# Sheet_CL-RB-01.net
KiCad netlist of a schematic drawn in Altium Designer
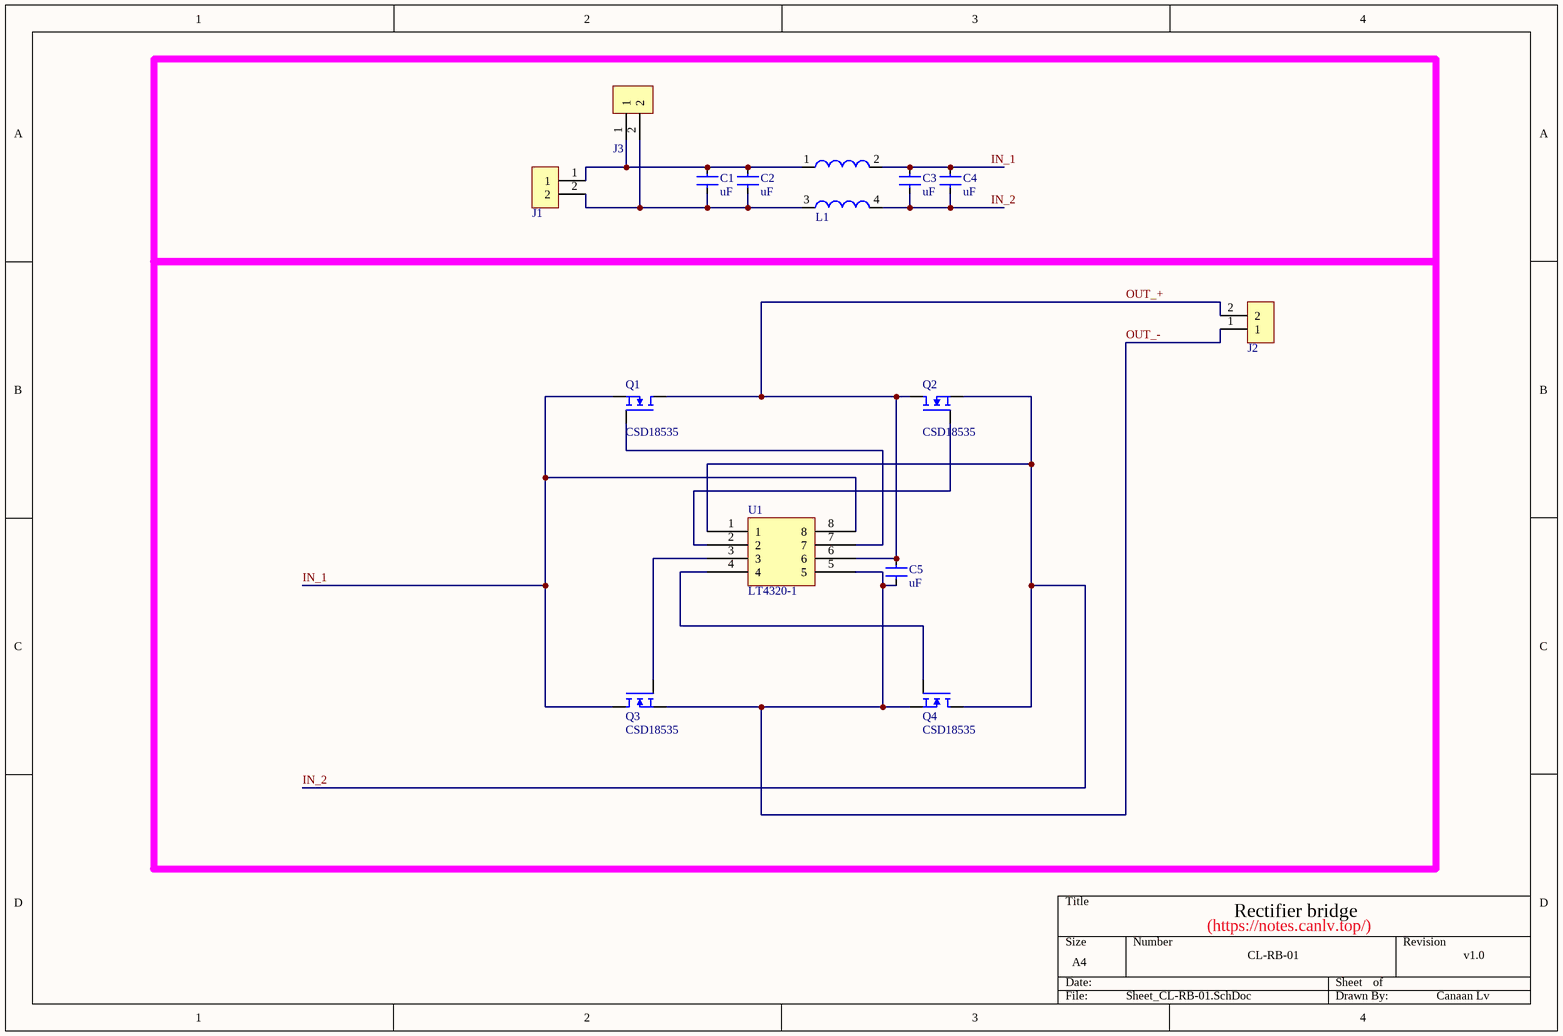
[diagram p0: Sheet_CL-RB-01.SchDoc]

(export (version "E")
  (design (tool "Eeschema 10.0.6"))
  (components
    (comp (ref "C1") (value "uF") (footprint "CAP-7.5-CP") (libsource (lib "电容") (part "C直插无极性")))
    (comp (ref "C2") (value "uF") (footprint "CAP-15") (libsource (lib "电容") (part "C直插无极性")))
    (comp (ref "C3") (value "uF") (footprint "CAP-15") (libsource (lib "电容") (part "C直插无极性")))
    (comp (ref "C4") (value "uF") (footprint "CAP-7.5-CP") (libsource (lib "电容") (part "C直插无极性")))
    (comp (ref "C5") (value "uF") (footprint "C0.254") (libsource (lib "电容") (part "C直插无极性")))
    (comp (ref "J1") (value "SIP-2") (footprint "9.5栅栏式接线端子") (libsource (lib "") (part "SIP-2_1")))
    (comp (ref "J2") (value "SIP-2") (footprint "9.5栅栏式接线端子") (libsource (lib "接插件") (part "SIP-2")))
    (comp (ref "J3") (value "SIP-2") (footprint "2.54XH接插件2P") (libsource (lib "接插件") (part "SIP-2")))
    (comp (ref "L1") (value "双电感") (footprint "L-CM(25*15*12)") (libsource (lib "电感") (part "双电感")))
    (comp (ref "Q1")
      (value "CSD18535")
      (footprint "TO-263-2")
      (description "N-Channel MOSFET")
      (libsource (lib "General") (part "N-MOSFET"))
    )
    (comp (ref "Q2")
      (value "CSD18535")
      (footprint "TO-263-2")
      (description "N-Channel MOSFET")
      (libsource (lib "General") (part "N-MOSFET"))
    )
    (comp (ref "Q3")
      (value "CSD18535")
      (footprint "TO-263-2")
      (description "N-Channel MOSFET")
      (libsource (lib "General") (part "N-MOSFET"))
    )
    (comp (ref "Q4")
      (value "CSD18535")
      (footprint "TO-263-2")
      (description "N-Channel MOSFET")
      (libsource (lib "General") (part "N-MOSFET"))
    )
    (comp (ref "U1") (value "LT4320-1") (footprint "DIP8") (libsource (lib "集成块") (part "IC8")))
  )
  (nets
    (net (code "1") (name "/IN_1") (class "Default")
      (node (ref "C3") (pin "1") (pinfunction "1_1") (pintype "passive"))
      (node (ref "C4") (pin "1") (pinfunction "1_1") (pintype "passive"))
      (node (ref "L1") (pin "2") (pinfunction "2_2") (pintype "passive"))
      (node (ref "Q1") (pin "3") (pinfunction "S_3") (pintype "passive"))
      (node (ref "Q3") (pin "2") (pinfunction "D_2") (pintype "passive"))
      (node (ref "U1") (pin "8") (pinfunction "8_8") (pintype "passive"))
    )
    (net (code "2") (name "/IN_2") (class "Default")
      (node (ref "C3") (pin "2") (pinfunction "2_2") (pintype "passive"))
      (node (ref "C4") (pin "2") (pinfunction "2_2") (pintype "passive"))
      (node (ref "L1") (pin "4") (pinfunction "4_4") (pintype "passive"))
      (node (ref "Q2") (pin "3") (pinfunction "S_3") (pintype "passive"))
      (node (ref "Q4") (pin "2") (pinfunction "D_2") (pintype "passive"))
      (node (ref "U1") (pin "1") (pinfunction "1_1") (pintype "passive"))
    )
    (net (code "3") (name "/OUT_+") (class "Default")
      (node (ref "C5") (pin "1") (pinfunction "1_1") (pintype "passive"))
      (node (ref "J2") (pin "2") (pinfunction "2_2") (pintype "passive"))
      (node (ref "Q1") (pin "2") (pinfunction "D_2") (pintype "passive"))
      (node (ref "Q2") (pin "2") (pinfunction "D_2") (pintype "passive"))
      (node (ref "U1") (pin "6") (pinfunction "6_6") (pintype "passive"))
    )
    (net (code "4") (name "/OUT_-") (class "Default")
      (node (ref "C5") (pin "2") (pinfunction "2_2") (pintype "passive"))
      (node (ref "J2") (pin "1") (pinfunction "1_1") (pintype "passive"))
      (node (ref "Q3") (pin "3") (pinfunction "S_3") (pintype "passive"))
      (node (ref "Q4") (pin "3") (pinfunction "S_3") (pintype "passive"))
      (node (ref "U1") (pin "5") (pinfunction "5_5") (pintype "passive"))
    )
    (net (code "5") (name "Net-(C1-Pad1)") (class "Default")
      (node (ref "C1") (pin "1") (pinfunction "1_1") (pintype "passive"))
      (node (ref "C2") (pin "1") (pinfunction "1_1") (pintype "passive"))
      (node (ref "J1") (pin "1") (pinfunction "1_1") (pintype "passive"))
      (node (ref "J3") (pin "1") (pinfunction "1_1") (pintype "passive"))
      (node (ref "L1") (pin "1") (pinfunction "1_1") (pintype "passive"))
    )
    (net (code "6") (name "Net-(C1-Pad2)") (class "Default")
      (node (ref "C1") (pin "2") (pinfunction "2_2") (pintype "passive"))
      (node (ref "C2") (pin "2") (pinfunction "2_2") (pintype "passive"))
      (node (ref "J1") (pin "2") (pinfunction "2_2") (pintype "passive"))
      (node (ref "J3") (pin "2") (pinfunction "2_2") (pintype "passive"))
      (node (ref "L1") (pin "3") (pinfunction "3_3") (pintype "passive"))
    )
    (net (code "7") (name "Net-(Q1-G)") (class "Default")
      (node (ref "Q1") (pin "1") (pinfunction "G_1") (pintype "passive"))
      (node (ref "U1") (pin "7") (pinfunction "7_7") (pintype "passive"))
    )
    (net (code "8") (name "Net-(Q2-G)") (class "Default")
      (node (ref "Q2") (pin "1") (pinfunction "G_1") (pintype "passive"))
      (node (ref "U1") (pin "2") (pinfunction "2_2") (pintype "passive"))
    )
    (net (code "9") (name "Net-(Q3-G)") (class "Default")
      (node (ref "Q3") (pin "1") (pinfunction "G_1") (pintype "passive"))
      (node (ref "U1") (pin "3") (pinfunction "3_3") (pintype "passive"))
    )
    (net (code "10") (name "Net-(Q4-G)") (class "Default")
      (node (ref "Q4") (pin "1") (pinfunction "G_1") (pintype "passive"))
      (node (ref "U1") (pin "4") (pinfunction "4_4") (pintype "passive"))
    )
  )
)
